# 24V_AC_SSR_Board_v1_0.net
KiCad netlist of a schematic drawn in EAGLE
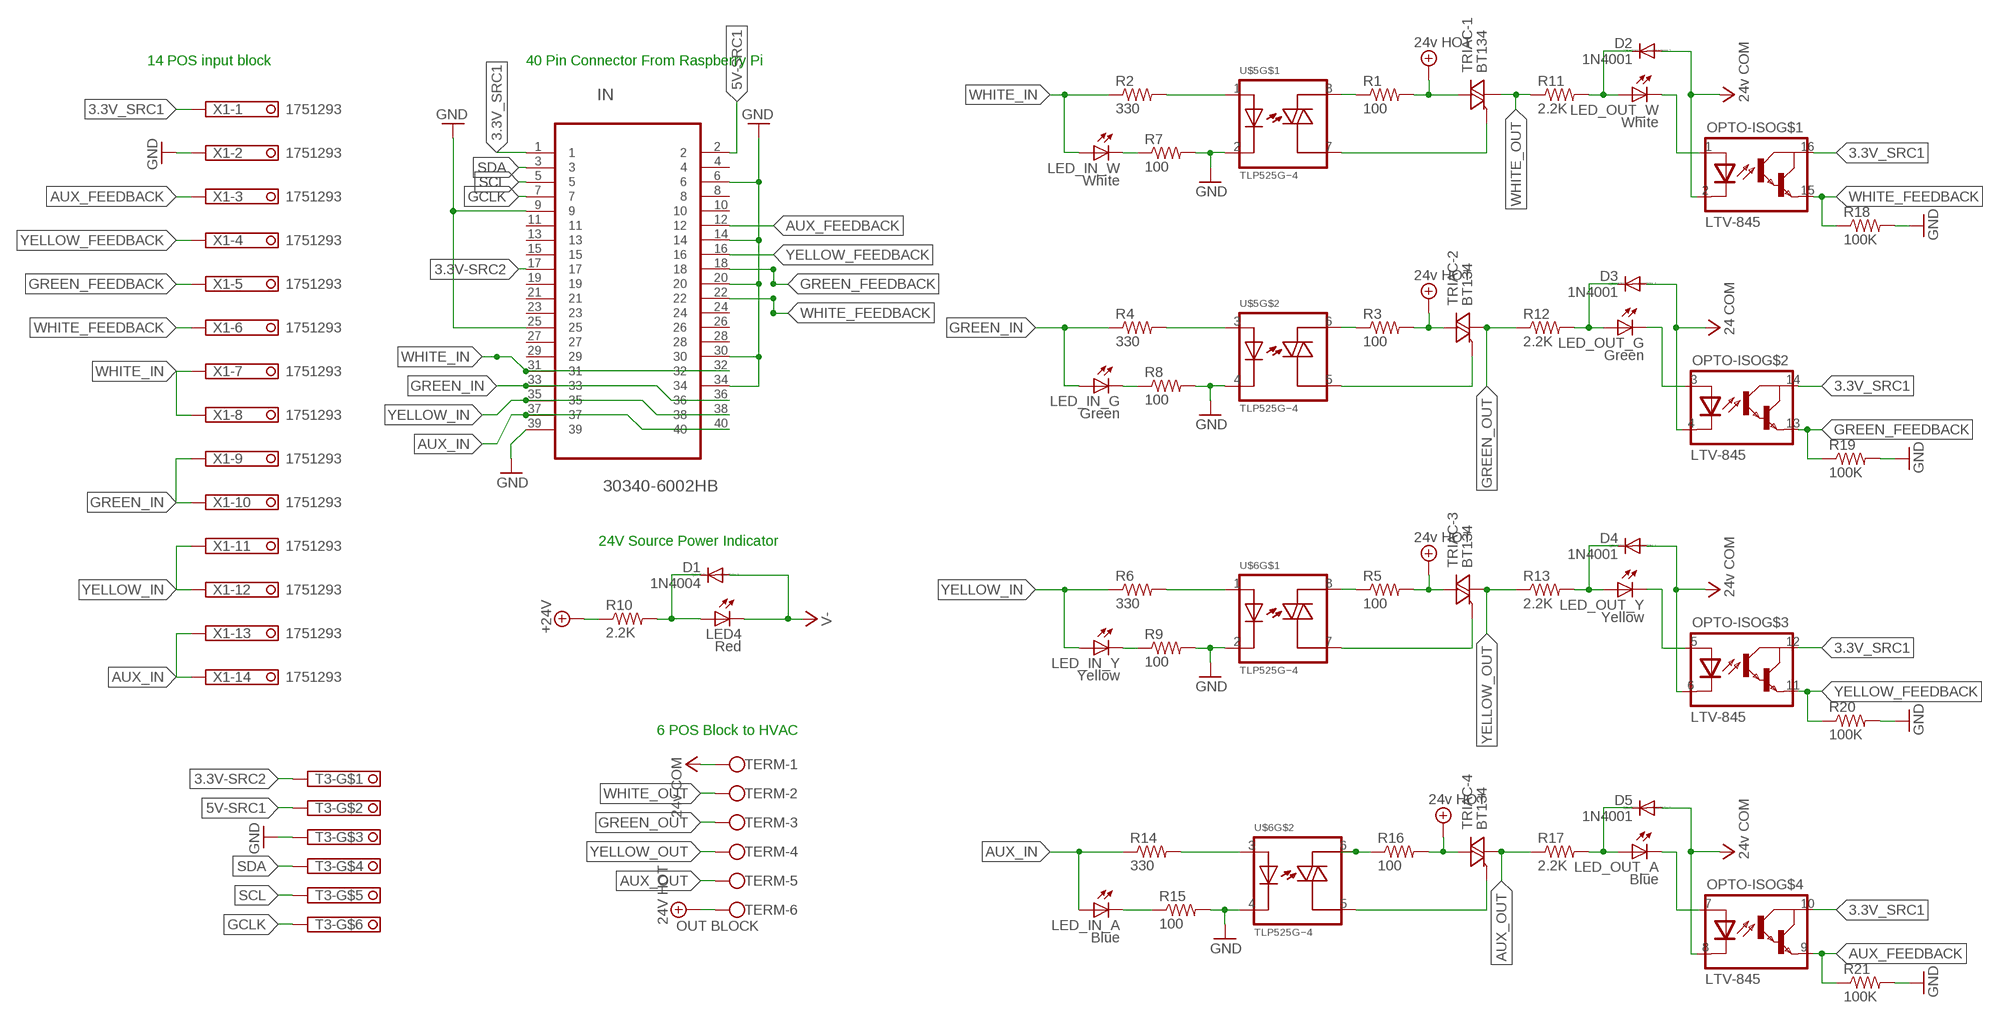
[diagram p0: schematic, sheet 1]

(export (version "E")
  (design (tool "Eeschema 10.0.6"))
  (components
    (comp (ref "D1")
      (value "1N4004")
      (footprint "eagle-import:DO41-10")
      (libsource (lib "eagle-import") (part "1N4004"))
    )
    (comp (ref "D2")
      (value "1N4001")
      (footprint "eagle-import:DO41-10")
      (libsource (lib "eagle-import") (part "1N4004"))
    )
    (comp (ref "D3")
      (value "1N4001")
      (footprint "eagle-import:DO41-10")
      (libsource (lib "eagle-import") (part "1N4004"))
    )
    (comp (ref "D4")
      (value "1N4001")
      (footprint "eagle-import:DO41-10")
      (libsource (lib "eagle-import") (part "1N4004"))
    )
    (comp (ref "D5")
      (value "1N4001")
      (footprint "eagle-import:DO41-10")
      (libsource (lib "eagle-import") (part "1N4004"))
    )
    (comp (ref "IN")
      (value "30340-6002HB")
      (footprint "eagle-import:3M_2540-6002UB")
      (fields (field (name "MPN") "2540-6002UB"))
      (libsource (lib "eagle-import") (part "2540-6002UB"))
    )
    (comp (ref "LED4")
      (value "Red")
      (footprint "eagle-import:LED3MM")
      (libsource (lib "eagle-import") (part "LED3MM"))
    )
    (comp (ref "LED_IN_A")
      (value "Blue")
      (footprint "eagle-import:LED3MM")
      (libsource (lib "eagle-import") (part "LED3MM"))
    )
    (comp (ref "LED_IN_G")
      (value "Green")
      (footprint "eagle-import:LED3MM")
      (libsource (lib "eagle-import") (part "LED3MM"))
    )
    (comp (ref "LED_IN_W")
      (value "White")
      (footprint "eagle-import:LED3MM")
      (libsource (lib "eagle-import") (part "LED3MM"))
    )
    (comp (ref "LED_IN_Y")
      (value "Yellow")
      (footprint "eagle-import:LED3MM")
      (libsource (lib "eagle-import") (part "LED3MM"))
    )
    (comp (ref "LED_OUT_A")
      (value "Blue")
      (footprint "eagle-import:LED3MM")
      (libsource (lib "eagle-import") (part "LED3MM"))
    )
    (comp (ref "LED_OUT_G")
      (value "Green")
      (footprint "eagle-import:LED3MM")
      (libsource (lib "eagle-import") (part "LED3MM"))
    )
    (comp (ref "LED_OUT_W")
      (value "White")
      (footprint "eagle-import:LED3MM")
      (libsource (lib "eagle-import") (part "LED3MM"))
    )
    (comp (ref "LED_OUT_Y")
      (value "Yellow")
      (footprint "eagle-import:LED3MM")
      (libsource (lib "eagle-import") (part "LED3MM"))
    )
    (comp (ref "OPTO-ISO")
      (value "LTV-845")
      (footprint "eagle-import:DIL16")
      (libsource (lib "eagle-import") (part "LTV-845"))
    )
    (comp (ref "R1")
      (value "100")
      (footprint "eagle-import:0204_7")
      (libsource (lib "eagle-import") (part "R-US_0204/7"))
    )
    (comp (ref "R2")
      (value "330")
      (footprint "eagle-import:0204_7")
      (libsource (lib "eagle-import") (part "R-US_0204/7"))
    )
    (comp (ref "R3")
      (value "100")
      (footprint "eagle-import:0204_7")
      (libsource (lib "eagle-import") (part "R-US_0204/7"))
    )
    (comp (ref "R4")
      (value "330")
      (footprint "eagle-import:0204_7")
      (libsource (lib "eagle-import") (part "R-US_0204/7"))
    )
    (comp (ref "R5")
      (value "100")
      (footprint "eagle-import:0204_7")
      (libsource (lib "eagle-import") (part "R-US_0204/7"))
    )
    (comp (ref "R6")
      (value "330")
      (footprint "eagle-import:0204_7")
      (libsource (lib "eagle-import") (part "R-US_0204/7"))
    )
    (comp (ref "R7")
      (value "100")
      (footprint "eagle-import:0204_7")
      (libsource (lib "eagle-import") (part "R-US_0204/7"))
    )
    (comp (ref "R8")
      (value "100")
      (footprint "eagle-import:0204_7")
      (libsource (lib "eagle-import") (part "R-US_0204/7"))
    )
    (comp (ref "R9")
      (value "100")
      (footprint "eagle-import:0204_7")
      (libsource (lib "eagle-import") (part "R-US_0204/7"))
    )
    (comp (ref "R10")
      (value "2.2K")
      (footprint "eagle-import:0204_7")
      (libsource (lib "eagle-import") (part "R-US_0204/7"))
    )
    (comp (ref "R11")
      (value "2.2K")
      (footprint "eagle-import:0204_7")
      (libsource (lib "eagle-import") (part "R-US_0204/7"))
    )
    (comp (ref "R12")
      (value "2.2K")
      (footprint "eagle-import:0204_7")
      (libsource (lib "eagle-import") (part "R-US_0204/7"))
    )
    (comp (ref "R13")
      (value "2.2K")
      (footprint "eagle-import:0204_7")
      (libsource (lib "eagle-import") (part "R-US_0204/7"))
    )
    (comp (ref "R14")
      (value "330")
      (footprint "eagle-import:0204_7")
      (libsource (lib "eagle-import") (part "R-US_0204/7"))
    )
    (comp (ref "R15")
      (value "100")
      (footprint "eagle-import:0204_7")
      (libsource (lib "eagle-import") (part "R-US_0204/7"))
    )
    (comp (ref "R16")
      (value "100")
      (footprint "eagle-import:0204_7")
      (libsource (lib "eagle-import") (part "R-US_0204/7"))
    )
    (comp (ref "R17")
      (value "2.2K")
      (footprint "eagle-import:0204_7")
      (libsource (lib "eagle-import") (part "R-US_0204/7"))
    )
    (comp (ref "R18")
      (value "100K")
      (footprint "eagle-import:0204_7")
      (libsource (lib "eagle-import") (part "R-US_0204/7"))
    )
    (comp (ref "R19")
      (value "100K")
      (footprint "eagle-import:0204_7")
      (libsource (lib "eagle-import") (part "R-US_0204/7"))
    )
    (comp (ref "R20")
      (value "100K")
      (footprint "eagle-import:0204_7")
      (libsource (lib "eagle-import") (part "R-US_0204/7"))
    )
    (comp (ref "R21")
      (value "100K")
      (footprint "eagle-import:0204_7")
      (libsource (lib "eagle-import") (part "R-US_0204/7"))
    )
    (comp (ref "T3-")
      (value "6-POS-SCREW-TERM-PT-3.5MM")
      (footprint "eagle-import:6-POS-SCREW-TERM-PT-3.5MM")
      (libsource (lib "eagle-import") (part "6-POS-SCREW-TERM-PT-3.5MM"))
    )
    (comp (ref "TERM")
      (value "OUT BLOCK")
      (footprint "eagle-import:W237-6")
      (libsource (lib "eagle-import") (part "W237-6"))
    )
    (comp (ref "TRIAC-1")
      (value "BT134")
      (footprint "eagle-import:SOT82")
      (libsource (lib "eagle-import") (part "BT134"))
    )
    (comp (ref "TRIAC-2")
      (value "BT134")
      (footprint "eagle-import:SOT82")
      (libsource (lib "eagle-import") (part "BT134"))
    )
    (comp (ref "TRIAC-3")
      (value "BT134")
      (footprint "eagle-import:SOT82")
      (libsource (lib "eagle-import") (part "BT134"))
    )
    (comp (ref "TRIAC-4")
      (value "BT134")
      (footprint "eagle-import:SOT82")
      (libsource (lib "eagle-import") (part "BT134"))
    )
    (comp (ref "U$5")
      (value "TLP525G−4")
      (footprint "eagle-import:DIL08")
      (libsource (lib "eagle-import") (part "TLP525G−4"))
    )
    (comp (ref "U$6")
      (value "TLP525G−4")
      (footprint "eagle-import:DIL08")
      (libsource (lib "eagle-import") (part "TLP525G−4"))
    )
    (comp (ref "X1")
      (value "1751293")
      (footprint "eagle-import:1751293")
      (libsource (lib "eagle-import") (part "1751293"))
    )
  )
  (nets
    (net (code "1") (name "+24V") (class "Default")
      (node (ref "R1") (pin "2") (pinfunction "2_2") (pintype "passive"))
      (node (ref "R10") (pin "1") (pinfunction "1_1") (pintype "passive"))
      (node (ref "R16") (pin "2") (pinfunction "2_2") (pintype "passive"))
      (node (ref "R3") (pin "2") (pinfunction "2_2") (pintype "passive"))
      (node (ref "R5") (pin "2") (pinfunction "2_2") (pintype "passive"))
      (node (ref "TERM") (pin "6") (pinfunction "KL_6") (pintype "passive"))
      (node (ref "TRIAC-1") (pin "2") (pinfunction "A2_2") (pintype "passive"))
      (node (ref "TRIAC-2") (pin "2") (pinfunction "A2_2") (pintype "passive"))
      (node (ref "TRIAC-3") (pin "2") (pinfunction "A2_2") (pintype "passive"))
      (node (ref "TRIAC-4") (pin "2") (pinfunction "A2_2") (pintype "passive"))
    )
    (net (code "2") (name "3.3V-SRC2") (class "Default")
      (node (ref "IN") (pin "17") (pinfunction "17_17") (pintype "passive"))
      (node (ref "T3-") (pin "1") (pinfunction "K_1") (pintype "passive"))
    )
    (net (code "3") (name "3.3V_SRC1") (class "Default")
      (node (ref "IN") (pin "1") (pinfunction "1_1") (pintype "passive"))
      (node (ref "OPTO-ISO") (pin "10") (pinfunction "COLLECTOR_10") (pintype "bidirectional"))
      (node (ref "OPTO-ISO") (pin "12") (pinfunction "COLLECTOR_12") (pintype "bidirectional"))
      (node (ref "OPTO-ISO") (pin "14") (pinfunction "COLLECTOR_14") (pintype "bidirectional"))
      (node (ref "OPTO-ISO") (pin "16") (pinfunction "COLLECTOR_16") (pintype "bidirectional"))
      (node (ref "X1") (pin "1") (pinfunction "K_1") (pintype "passive"))
    )
    (net (code "4") (name "5V-SRC1") (class "Default")
      (node (ref "IN") (pin "2") (pinfunction "2_2") (pintype "passive"))
      (node (ref "T3-") (pin "2") (pinfunction "K_2") (pintype "passive"))
    )
    (net (code "5") (name "24 COM") (class "Default")
      (node (ref "D1") (pin "A") (pinfunction "A_A") (pintype "passive"))
      (node (ref "D2") (pin "A") (pinfunction "A_A") (pintype "passive"))
      (node (ref "D3") (pin "A") (pinfunction "A_A") (pintype "passive"))
      (node (ref "D4") (pin "A") (pinfunction "A_A") (pintype "passive"))
      (node (ref "D5") (pin "A") (pinfunction "A_A") (pintype "passive"))
      (node (ref "LED4") (pin "K") (pinfunction "C_K") (pintype "passive"))
      (node (ref "OPTO-ISO") (pin "2") (pinfunction "CATHODE_2") (pintype "bidirectional"))
      (node (ref "OPTO-ISO") (pin "4") (pinfunction "CATHODE_4") (pintype "bidirectional"))
      (node (ref "OPTO-ISO") (pin "6") (pinfunction "CATHODE_6") (pintype "bidirectional"))
      (node (ref "OPTO-ISO") (pin "8") (pinfunction "CATHODE_8") (pintype "bidirectional"))
      (node (ref "TERM") (pin "1") (pinfunction "KL_1") (pintype "passive"))
    )
    (net (code "6") (name "AUX_FEEDBACK") (class "Default")
      (node (ref "IN") (pin "12") (pinfunction "12_12") (pintype "passive"))
      (node (ref "OPTO-ISO") (pin "9") (pinfunction "EMITTER_9") (pintype "bidirectional"))
      (node (ref "R21") (pin "1") (pinfunction "1_1") (pintype "passive"))
      (node (ref "X1") (pin "3") (pinfunction "K_3") (pintype "passive"))
    )
    (net (code "7") (name "AUX_IN") (class "Default")
      (node (ref "IN") (pin "37") (pinfunction "37_37") (pintype "passive"))
      (node (ref "IN") (pin "40") (pinfunction "40_40") (pintype "passive"))
      (node (ref "LED_IN_A") (pin "A") (pinfunction "A_A") (pintype "passive"))
      (node (ref "R14") (pin "1") (pinfunction "1_1") (pintype "passive"))
      (node (ref "X1") (pin "13") (pinfunction "K_13") (pintype "passive"))
      (node (ref "X1") (pin "14") (pinfunction "K_14") (pintype "passive"))
    )
    (net (code "8") (name "AUX_OUT") (class "Default")
      (node (ref "R17") (pin "1") (pinfunction "1_1") (pintype "passive"))
      (node (ref "TERM") (pin "5") (pinfunction "KL_5") (pintype "passive"))
      (node (ref "TRIAC-4") (pin "1") (pinfunction "A1_1") (pintype "passive"))
    )
    (net (code "9") (name "GCLK") (class "Default")
      (node (ref "IN") (pin "7") (pinfunction "7_7") (pintype "passive"))
      (node (ref "T3-") (pin "6") (pinfunction "K_6") (pintype "passive"))
    )
    (net (code "10") (name "GND") (class "Default")
      (node (ref "IN") (pin "14") (pinfunction "14_14") (pintype "passive"))
      (node (ref "IN") (pin "20") (pinfunction "20_20") (pintype "passive"))
      (node (ref "IN") (pin "25") (pinfunction "25_25") (pintype "passive"))
      (node (ref "IN") (pin "30") (pinfunction "30_30") (pintype "passive"))
      (node (ref "IN") (pin "34") (pinfunction "34_34") (pintype "passive"))
      (node (ref "IN") (pin "39") (pinfunction "39_39") (pintype "passive"))
      (node (ref "IN") (pin "6") (pinfunction "6_6") (pintype "passive"))
      (node (ref "IN") (pin "9") (pinfunction "9_9") (pintype "passive"))
      (node (ref "R15") (pin "2") (pinfunction "2_2") (pintype "passive"))
      (node (ref "R18") (pin "2") (pinfunction "2_2") (pintype "passive"))
      (node (ref "R19") (pin "2") (pinfunction "2_2") (pintype "passive"))
      (node (ref "R20") (pin "2") (pinfunction "2_2") (pintype "passive"))
      (node (ref "R21") (pin "2") (pinfunction "2_2") (pintype "passive"))
      (node (ref "R7") (pin "2") (pinfunction "2_2") (pintype "passive"))
      (node (ref "R8") (pin "2") (pinfunction "2_2") (pintype "passive"))
      (node (ref "R9") (pin "2") (pinfunction "2_2") (pintype "passive"))
      (node (ref "T3-") (pin "3") (pinfunction "K_3") (pintype "passive"))
      (node (ref "U$5") (pin "2") (pinfunction "CATHODE_2") (pintype "bidirectional"))
      (node (ref "U$5") (pin "4") (pinfunction "CATHODE_4") (pintype "bidirectional"))
      (node (ref "U$6") (pin "2") (pinfunction "CATHODE_2") (pintype "bidirectional"))
      (node (ref "U$6") (pin "4") (pinfunction "CATHODE_4") (pintype "bidirectional"))
      (node (ref "X1") (pin "2") (pinfunction "K_2") (pintype "passive"))
    )
    (net (code "11") (name "GREEN_FEEDBACK") (class "Default")
      (node (ref "IN") (pin "18") (pinfunction "18_18") (pintype "passive"))
      (node (ref "OPTO-ISO") (pin "13") (pinfunction "EMITTER_13") (pintype "bidirectional"))
      (node (ref "R19") (pin "1") (pinfunction "1_1") (pintype "passive"))
      (node (ref "X1") (pin "5") (pinfunction "K_5") (pintype "passive"))
    )
    (net (code "12") (name "GREEN_IN") (class "Default")
      (node (ref "IN") (pin "33") (pinfunction "33_33") (pintype "passive"))
      (node (ref "IN") (pin "36") (pinfunction "36_36") (pintype "passive"))
      (node (ref "LED_IN_G") (pin "A") (pinfunction "A_A") (pintype "passive"))
      (node (ref "R4") (pin "1") (pinfunction "1_1") (pintype "passive"))
      (node (ref "X1") (pin "10") (pinfunction "K_10") (pintype "passive"))
      (node (ref "X1") (pin "9") (pinfunction "K_9") (pintype "passive"))
    )
    (net (code "13") (name "GREEN_OUT") (class "Default")
      (node (ref "R12") (pin "1") (pinfunction "1_1") (pintype "passive"))
      (node (ref "TERM") (pin "3") (pinfunction "KL_3") (pintype "passive"))
      (node (ref "TRIAC-2") (pin "1") (pinfunction "A1_1") (pintype "passive"))
    )
    (net (code "14") (name "Net-(D1-PadC)") (class "Default")
      (node (ref "D1") (pin "C") (pinfunction "C_C") (pintype "passive"))
      (node (ref "LED4") (pin "A") (pinfunction "A_A") (pintype "passive"))
      (node (ref "R10") (pin "2") (pinfunction "2_2") (pintype "passive"))
    )
    (net (code "15") (name "Net-(D2-PadC)") (class "Default")
      (node (ref "D2") (pin "C") (pinfunction "C_C") (pintype "passive"))
      (node (ref "LED_OUT_W") (pin "A") (pinfunction "A_A") (pintype "passive"))
      (node (ref "R11") (pin "2") (pinfunction "2_2") (pintype "passive"))
    )
    (net (code "16") (name "Net-(D3-PadC)") (class "Default")
      (node (ref "D3") (pin "C") (pinfunction "C_C") (pintype "passive"))
      (node (ref "LED_OUT_G") (pin "A") (pinfunction "A_A") (pintype "passive"))
      (node (ref "R12") (pin "2") (pinfunction "2_2") (pintype "passive"))
    )
    (net (code "17") (name "Net-(D4-PadC)") (class "Default")
      (node (ref "D4") (pin "C") (pinfunction "C_C") (pintype "passive"))
      (node (ref "LED_OUT_Y") (pin "A") (pinfunction "A_A") (pintype "passive"))
      (node (ref "R13") (pin "2") (pinfunction "2_2") (pintype "passive"))
    )
    (net (code "18") (name "Net-(D5-PadC)") (class "Default")
      (node (ref "D5") (pin "C") (pinfunction "C_C") (pintype "passive"))
      (node (ref "LED_OUT_A") (pin "A") (pinfunction "A_A") (pintype "passive"))
      (node (ref "R17") (pin "2") (pinfunction "2_2") (pintype "passive"))
    )
    (net (code "19") (name "Net-(LED_IN_A-C)") (class "Default")
      (node (ref "LED_IN_A") (pin "K") (pinfunction "C_K") (pintype "passive"))
      (node (ref "R15") (pin "1") (pinfunction "1_1") (pintype "passive"))
    )
    (net (code "20") (name "Net-(LED_IN_G-C)") (class "Default")
      (node (ref "LED_IN_G") (pin "K") (pinfunction "C_K") (pintype "passive"))
      (node (ref "R8") (pin "1") (pinfunction "1_1") (pintype "passive"))
    )
    (net (code "21") (name "Net-(LED_IN_W-C)") (class "Default")
      (node (ref "LED_IN_W") (pin "K") (pinfunction "C_K") (pintype "passive"))
      (node (ref "R7") (pin "1") (pinfunction "1_1") (pintype "passive"))
    )
    (net (code "22") (name "Net-(LED_IN_Y-C)") (class "Default")
      (node (ref "LED_IN_Y") (pin "K") (pinfunction "C_K") (pintype "passive"))
      (node (ref "R9") (pin "1") (pinfunction "1_1") (pintype "passive"))
    )
    (net (code "23") (name "Net-(LED_OUT_A-C)") (class "Default")
      (node (ref "LED_OUT_A") (pin "K") (pinfunction "C_K") (pintype "passive"))
      (node (ref "OPTO-ISO") (pin "7") (pinfunction "ANNODE_7") (pintype "bidirectional"))
    )
    (net (code "24") (name "Net-(LED_OUT_G-C)") (class "Default")
      (node (ref "LED_OUT_G") (pin "K") (pinfunction "C_K") (pintype "passive"))
      (node (ref "OPTO-ISO") (pin "3") (pinfunction "ANNODE_3") (pintype "bidirectional"))
    )
    (net (code "25") (name "Net-(LED_OUT_W-C)") (class "Default")
      (node (ref "LED_OUT_W") (pin "K") (pinfunction "C_K") (pintype "passive"))
      (node (ref "OPTO-ISO") (pin "1") (pinfunction "ANNODE_1") (pintype "bidirectional"))
    )
    (net (code "26") (name "Net-(LED_OUT_Y-C)") (class "Default")
      (node (ref "LED_OUT_Y") (pin "K") (pinfunction "C_K") (pintype "passive"))
      (node (ref "OPTO-ISO") (pin "5") (pinfunction "ANNODE_5") (pintype "bidirectional"))
    )
    (net (code "27") (name "Net-(TRIAC-1-G)") (class "Default")
      (node (ref "TRIAC-1") (pin "3") (pinfunction "G_3") (pintype "passive"))
      (node (ref "U$5") (pin "7") (pinfunction "T1_7") (pintype "bidirectional"))
    )
    (net (code "28") (name "Net-(TRIAC-2-G)") (class "Default")
      (node (ref "TRIAC-2") (pin "3") (pinfunction "G_3") (pintype "passive"))
      (node (ref "U$5") (pin "5") (pinfunction "T1_5") (pintype "bidirectional"))
    )
    (net (code "29") (name "Net-(TRIAC-3-G)") (class "Default")
      (node (ref "TRIAC-3") (pin "3") (pinfunction "G_3") (pintype "passive"))
      (node (ref "U$6") (pin "7") (pinfunction "T1_7") (pintype "bidirectional"))
    )
    (net (code "30") (name "Net-(TRIAC-4-G)") (class "Default")
      (node (ref "TRIAC-4") (pin "3") (pinfunction "G_3") (pintype "passive"))
      (node (ref "U$6") (pin "5") (pinfunction "T1_5") (pintype "bidirectional"))
    )
    (net (code "31") (name "Net-(U$5A-ANNODE)") (class "Default")
      (node (ref "R2") (pin "2") (pinfunction "2_2") (pintype "passive"))
      (node (ref "U$5") (pin "1") (pinfunction "ANNODE_1") (pintype "bidirectional"))
    )
    (net (code "32") (name "Net-(U$5A-T2)") (class "Default")
      (node (ref "R1") (pin "1") (pinfunction "1_1") (pintype "passive"))
      (node (ref "U$5") (pin "8") (pinfunction "T2_8") (pintype "bidirectional"))
    )
    (net (code "33") (name "Net-(U$5B-ANNODE)") (class "Default")
      (node (ref "R4") (pin "2") (pinfunction "2_2") (pintype "passive"))
      (node (ref "U$5") (pin "3") (pinfunction "ANNODE_3") (pintype "bidirectional"))
    )
    (net (code "34") (name "Net-(U$5B-T2)") (class "Default")
      (node (ref "R3") (pin "1") (pinfunction "1_1") (pintype "passive"))
      (node (ref "U$5") (pin "6") (pinfunction "T2_6") (pintype "bidirectional"))
    )
    (net (code "35") (name "Net-(U$6A-ANNODE)") (class "Default")
      (node (ref "R6") (pin "2") (pinfunction "2_2") (pintype "passive"))
      (node (ref "U$6") (pin "1") (pinfunction "ANNODE_1") (pintype "bidirectional"))
    )
    (net (code "36") (name "Net-(U$6A-T2)") (class "Default")
      (node (ref "R5") (pin "1") (pinfunction "1_1") (pintype "passive"))
      (node (ref "U$6") (pin "8") (pinfunction "T2_8") (pintype "bidirectional"))
    )
    (net (code "37") (name "Net-(U$6B-ANNODE)") (class "Default")
      (node (ref "R14") (pin "2") (pinfunction "2_2") (pintype "passive"))
      (node (ref "U$6") (pin "3") (pinfunction "ANNODE_3") (pintype "bidirectional"))
    )
    (net (code "38") (name "Net-(U$6B-T2)") (class "Default")
      (node (ref "R16") (pin "1") (pinfunction "1_1") (pintype "passive"))
      (node (ref "U$6") (pin "6") (pinfunction "T2_6") (pintype "bidirectional"))
    )
    (net (code "39") (name "SCL") (class "Default")
      (node (ref "IN") (pin "5") (pinfunction "5_5") (pintype "passive"))
      (node (ref "T3-") (pin "5") (pinfunction "K_5") (pintype "passive"))
    )
    (net (code "40") (name "SDA") (class "Default")
      (node (ref "IN") (pin "3") (pinfunction "3_3") (pintype "passive"))
      (node (ref "T3-") (pin "4") (pinfunction "K_4") (pintype "passive"))
    )
    (net (code "41") (name "WHITE_FEEDBACK") (class "Default")
      (node (ref "IN") (pin "22") (pinfunction "22_22") (pintype "passive"))
      (node (ref "OPTO-ISO") (pin "15") (pinfunction "EMITTER_15") (pintype "bidirectional"))
      (node (ref "R18") (pin "1") (pinfunction "1_1") (pintype "passive"))
      (node (ref "X1") (pin "6") (pinfunction "K_6") (pintype "passive"))
    )
    (net (code "42") (name "WHITE_IN") (class "Default")
      (node (ref "IN") (pin "31") (pinfunction "31_31") (pintype "passive"))
      (node (ref "IN") (pin "32") (pinfunction "32_32") (pintype "passive"))
      (node (ref "LED_IN_W") (pin "A") (pinfunction "A_A") (pintype "passive"))
      (node (ref "R2") (pin "1") (pinfunction "1_1") (pintype "passive"))
      (node (ref "X1") (pin "7") (pinfunction "K_7") (pintype "passive"))
      (node (ref "X1") (pin "8") (pinfunction "K_8") (pintype "passive"))
    )
    (net (code "43") (name "WHITE_OUT") (class "Default")
      (node (ref "R11") (pin "1") (pinfunction "1_1") (pintype "passive"))
      (node (ref "TERM") (pin "2") (pinfunction "KL_2") (pintype "passive"))
      (node (ref "TRIAC-1") (pin "1") (pinfunction "A1_1") (pintype "passive"))
    )
    (net (code "44") (name "YELLOW_FEEDBACK") (class "Default")
      (node (ref "IN") (pin "16") (pinfunction "16_16") (pintype "passive"))
      (node (ref "OPTO-ISO") (pin "11") (pinfunction "EMITTER_11") (pintype "bidirectional"))
      (node (ref "R20") (pin "1") (pinfunction "1_1") (pintype "passive"))
      (node (ref "X1") (pin "4") (pinfunction "K_4") (pintype "passive"))
    )
    (net (code "45") (name "YELLOW_IN") (class "Default")
      (node (ref "IN") (pin "35") (pinfunction "35_35") (pintype "passive"))
      (node (ref "IN") (pin "38") (pinfunction "38_38") (pintype "passive"))
      (node (ref "LED_IN_Y") (pin "A") (pinfunction "A_A") (pintype "passive"))
      (node (ref "R6") (pin "1") (pinfunction "1_1") (pintype "passive"))
      (node (ref "X1") (pin "11") (pinfunction "K_11") (pintype "passive"))
      (node (ref "X1") (pin "12") (pinfunction "K_12") (pintype "passive"))
    )
    (net (code "46") (name "YELLOW_OUT") (class "Default")
      (node (ref "R13") (pin "1") (pinfunction "1_1") (pintype "passive"))
      (node (ref "TERM") (pin "4") (pinfunction "KL_4") (pintype "passive"))
      (node (ref "TRIAC-3") (pin "1") (pinfunction "A1_1") (pintype "passive"))
    )
    (net (code "47") (name "unconnected-(IN-Pad4)") (class "Default")
      (node (ref "IN") (pin "4") (pinfunction "4_4") (pintype "passive"))
    )
    (net (code "48") (name "unconnected-(IN-Pad8)") (class "Default")
      (node (ref "IN") (pin "8") (pinfunction "8_8") (pintype "passive"))
    )
    (net (code "49") (name "unconnected-(IN-Pad10)") (class "Default")
      (node (ref "IN") (pin "10") (pinfunction "10_10") (pintype "passive"))
    )
    (net (code "50") (name "unconnected-(IN-Pad11)") (class "Default")
      (node (ref "IN") (pin "11") (pinfunction "11_11") (pintype "passive"))
    )
    (net (code "51") (name "unconnected-(IN-Pad13)") (class "Default")
      (node (ref "IN") (pin "13") (pinfunction "13_13") (pintype "passive"))
    )
    (net (code "52") (name "unconnected-(IN-Pad15)") (class "Default")
      (node (ref "IN") (pin "15") (pinfunction "15_15") (pintype "passive"))
    )
    (net (code "53") (name "unconnected-(IN-Pad19)") (class "Default")
      (node (ref "IN") (pin "19") (pinfunction "19_19") (pintype "passive"))
    )
    (net (code "54") (name "unconnected-(IN-Pad21)") (class "Default")
      (node (ref "IN") (pin "21") (pinfunction "21_21") (pintype "passive"))
    )
    (net (code "55") (name "unconnected-(IN-Pad23)") (class "Default")
      (node (ref "IN") (pin "23") (pinfunction "23_23") (pintype "passive"))
    )
    (net (code "56") (name "unconnected-(IN-Pad24)") (class "Default")
      (node (ref "IN") (pin "24") (pinfunction "24_24") (pintype "passive"))
    )
    (net (code "57") (name "unconnected-(IN-Pad26)") (class "Default")
      (node (ref "IN") (pin "26") (pinfunction "26_26") (pintype "passive"))
    )
    (net (code "58") (name "unconnected-(IN-Pad27)") (class "Default")
      (node (ref "IN") (pin "27") (pinfunction "27_27") (pintype "passive"))
    )
    (net (code "59") (name "unconnected-(IN-Pad28)") (class "Default")
      (node (ref "IN") (pin "28") (pinfunction "28_28") (pintype "passive"))
    )
    (net (code "60") (name "unconnected-(IN-Pad29)") (class "Default")
      (node (ref "IN") (pin "29") (pinfunction "29_29") (pintype "passive"))
    )
  )
)
